# espduckdns_sch-v1.net
KiCad netlist of a schematic drawn in EAGLE
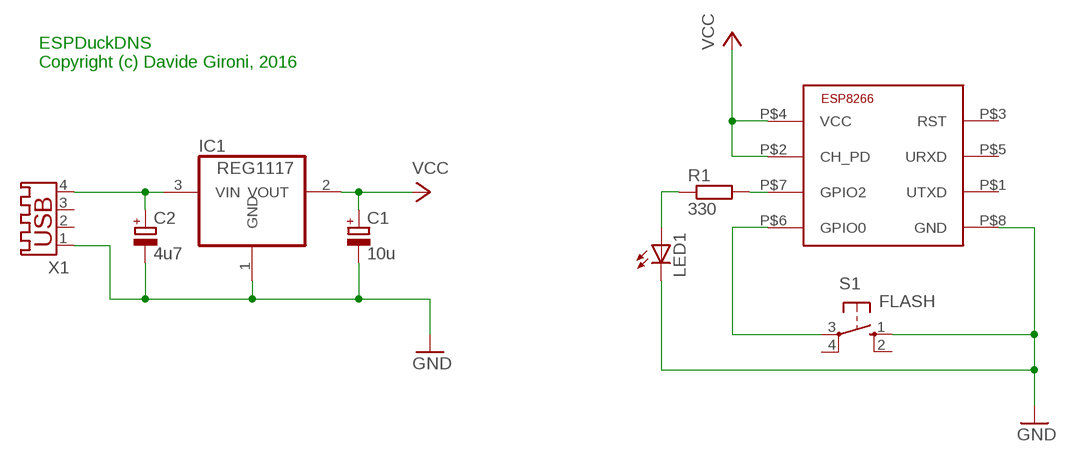
[diagram p0: schematic, sheet 1]

(export (version "E")
  (design (tool "Eeschema 10.0.6"))
  (components
    (comp (ref "C1")
      (value "10u")
      (footprint "eagle-import:E2,5-6E")
      (libsource (lib "eagle-import") (part "CPOL-EUE2,5-6E"))
    )
    (comp (ref "C2")
      (value "4u7")
      (footprint "eagle-import:E2,5-6E")
      (libsource (lib "eagle-import") (part "CPOL-EUE2,5-6E"))
    )
    (comp (ref "IC1")
      (value "REG1117")
      (footprint "eagle-import:SOT223")
      (libsource (lib "eagle-import") (part "REG1117"))
    )
    (comp (ref "LED1")
      (value "LED3MM")
      (footprint "eagle-import:LED3MM")
      (libsource (lib "eagle-import") (part "LED3MM"))
    )
    (comp (ref "R1")
      (value "330")
      (footprint "eagle-import:0204_7")
      (libsource (lib "eagle-import") (part "R-EU_0204/7"))
    )
    (comp (ref "S1")
      (value "FLASH")
      (footprint "eagle-import:B3F-10XX")
      (fields (field (name "MPN") "B3F-1000"))
      (libsource (lib "eagle-import") (part "10-XX"))
    )
    (comp (ref "U$1")
      (value "ESP8266-01")
      (footprint "eagle-import:ESP-01")
      (libsource (lib "eagle-import") (part "ESP8266-01"))
    )
    (comp (ref "X1")
      (value "USB-A003")
      (footprint "eagle-import:USB-A003")
      (libsource (lib "eagle-import") (part "USB-A003"))
    )
  )
  (nets
    (net (code "1") (name "GND") (class "Default")
      (node (ref "C1") (pin "-") (pinfunction "-_-") (pintype "passive"))
      (node (ref "C2") (pin "-") (pinfunction "-_-") (pintype "passive"))
      (node (ref "IC1") (pin "1") (pinfunction "GND_1") (pintype "power_in"))
      (node (ref "LED1") (pin "K") (pinfunction "C_K") (pintype "passive"))
      (node (ref "S1") (pin "1") (pinfunction "S_1") (pintype "passive"))
      (node (ref "U$1") (pin "P$8") (pinfunction "GND_P$8") (pintype "bidirectional"))
      (node (ref "X1") (pin "1") (pinfunction "1_1") (pintype "passive"))
    )
    (net (code "2") (name "Net-(IC1-VIN)") (class "Default")
      (node (ref "C2") (pin "+") (pinfunction "+_+") (pintype "passive"))
      (node (ref "IC1") (pin "3") (pinfunction "VIN_3") (pintype "input"))
      (node (ref "X1") (pin "4") (pinfunction "4_4") (pintype "passive"))
    )
    (net (code "3") (name "Net-(LED1-PadA)") (class "Default")
      (node (ref "LED1") (pin "A") (pinfunction "A_A") (pintype "passive"))
      (node (ref "R1") (pin "1") (pinfunction "1_1") (pintype "passive"))
    )
    (net (code "4") (name "Net-(S1-P)") (class "Default")
      (node (ref "S1") (pin "3") (pinfunction "P_3") (pintype "passive"))
      (node (ref "U$1") (pin "P$6") (pinfunction "GPIO0_P$6") (pintype "bidirectional"))
    )
    (net (code "5") (name "Net-(U$1-GPIO2)") (class "Default")
      (node (ref "R1") (pin "2") (pinfunction "2_2") (pintype "passive"))
      (node (ref "U$1") (pin "P$7") (pinfunction "GPIO2_P$7") (pintype "bidirectional"))
    )
    (net (code "6") (name "VCC") (class "Default")
      (node (ref "C1") (pin "+") (pinfunction "+_+") (pintype "passive"))
      (node (ref "IC1") (pin "2") (pinfunction "VOUT_2") (pintype "output"))
      (node (ref "U$1") (pin "P$2") (pinfunction "CH_PD_P$2") (pintype "bidirectional"))
      (node (ref "U$1") (pin "P$4") (pinfunction "VCC_P$4") (pintype "bidirectional"))
    )
    (net (code "7") (name "unconnected-(S1-P1-Pad4)") (class "Default")
      (node (ref "S1") (pin "4") (pinfunction "P1_4") (pintype "passive"))
    )
    (net (code "8") (name "unconnected-(S1-S1-Pad2)") (class "Default")
      (node (ref "S1") (pin "2") (pinfunction "S1_2") (pintype "passive"))
    )
    (net (code "9") (name "unconnected-(U$1-RST-PadP$3)") (class "Default")
      (node (ref "U$1") (pin "P$3") (pinfunction "RST_P$3") (pintype "bidirectional"))
    )
    (net (code "10") (name "unconnected-(U$1-URXD-PadP$5)") (class "Default")
      (node (ref "U$1") (pin "P$5") (pinfunction "URXD_P$5") (pintype "bidirectional"))
    )
    (net (code "11") (name "unconnected-(U$1-UTXD-PadP$1)") (class "Default")
      (node (ref "U$1") (pin "P$1") (pinfunction "UTXD_P$1") (pintype "bidirectional"))
    )
    (net (code "12") (name "unconnected-(X1-Pad2)") (class "Default")
      (node (ref "X1") (pin "2") (pinfunction "2_2") (pintype "passive"))
    )
    (net (code "13") (name "unconnected-(X1-Pad3)") (class "Default")
      (node (ref "X1") (pin "3") (pinfunction "3_3") (pintype "passive"))
    )
  )
)
